# OSC_PLL_SARDC_OPTeFUSE.net
KiCad netlist of a schematic drawn in Altium Designer
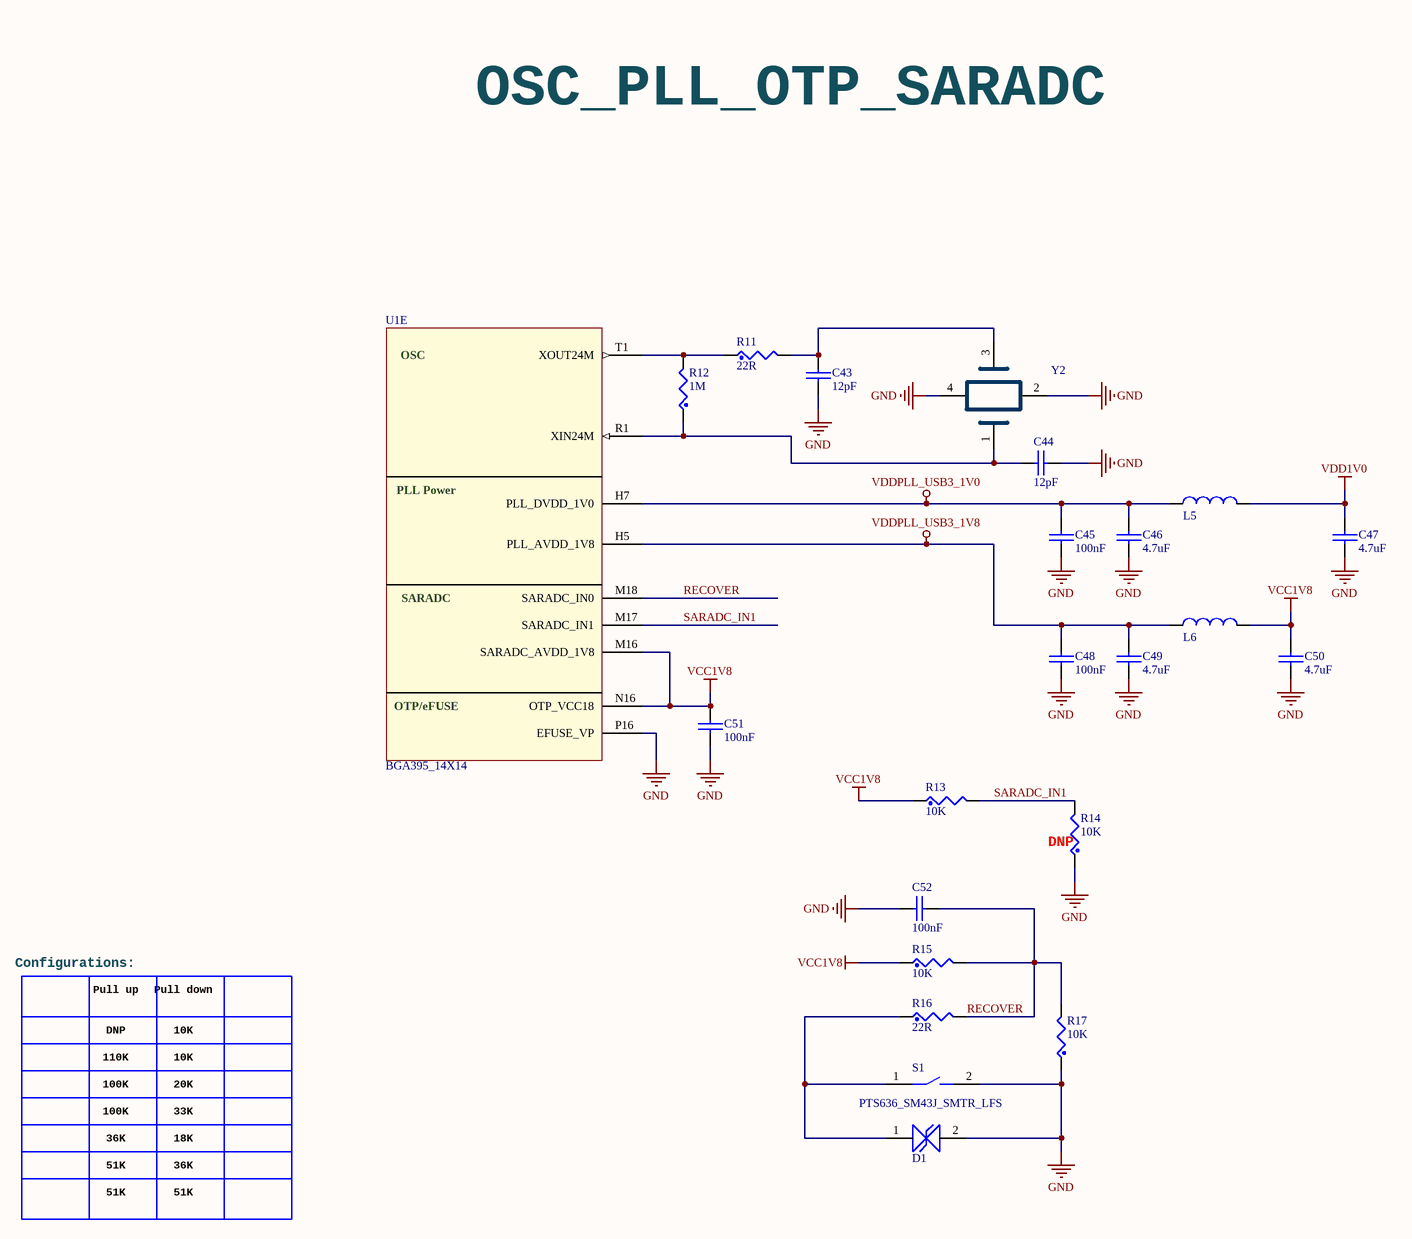
[diagram p0: OSC_PLL_SARDC_OPTeFUSE.SchDoc]

(export (version "E")
  (design (tool "Eeschema 10.0.6"))
  (components
    (comp (ref "C43")
      (value "12pF")
      (footprint "0402_CC - C")
      (libsource (lib "AAR_RockChip_RK3328") (part "CAP_NP"))
    )
    (comp (ref "C44")
      (value "12pF")
      (footprint "0402_CC - C")
      (libsource (lib "AAR_RockChip_RK3328") (part "CAP_NP"))
    )
    (comp (ref "C45")
      (value "100nF")
      (footprint "0402_CC - C")
      (libsource (lib "AAR_RockChip_RK3328") (part "CAP_NP"))
    )
    (comp (ref "C46")
      (value "4.7uF")
      (footprint "0402_CC - C")
      (libsource (lib "AAR_RockChip_RK3328") (part "CAP_NP"))
    )
    (comp (ref "C47")
      (value "4.7uF")
      (footprint "0402_CC - C")
      (libsource (lib "AAR_RockChip_RK3328") (part "CAP_NP"))
    )
    (comp (ref "C48")
      (value "100nF")
      (footprint "0402_CC - C")
      (libsource (lib "AAR_RockChip_RK3328") (part "CAP_NP"))
    )
    (comp (ref "C49")
      (value "4.7uF")
      (footprint "0402_CC - C")
      (libsource (lib "AAR_RockChip_RK3328") (part "CAP_NP"))
    )
    (comp (ref "C50")
      (value "4.7uF")
      (footprint "0402_CC - C")
      (libsource (lib "AAR_RockChip_RK3328") (part "CAP_NP"))
    )
    (comp (ref "C51")
      (value "100nF")
      (footprint "0402_CC - C")
      (libsource (lib "AAR_RockChip_RK3328") (part "CAP_NP"))
    )
    (comp (ref "C52")
      (value "100nF")
      (footprint "0402_CC - C")
      (libsource (lib "AAR_RockChip_RK3328") (part "CAP_NP"))
    )
    (comp (ref "D1")
      (value "TVS")
      (footprint "SODFL100X45-2N")
      (fields (field (name "MFR_PART_NO") "ESD5451N-2/TR") (field (name "LCSC PART #") "C239604"))
      (libsource (lib "AAR_RockChip_RK3328") (part "ESD5451N"))
    )
    (comp (ref "L5")
      (value "INDCHIP")
      (footprint "0603_C_Inductor")
      (description "Fixed Inductors  TDK, By AAR")
      (libsource (lib "AAR_RockChip_RK3328") (part "INDCHIP"))
    )
    (comp (ref "L6")
      (value "INDCHIP")
      (footprint "0603_C_Inductor")
      (description "Fixed Inductors  TDK, By AAR")
      (libsource (lib "AAR_RockChip_RK3328") (part "INDCHIP"))
    )
    (comp (ref "R11")
      (value "22R")
      (footprint "0402_CR")
      (libsource (lib "AAR_RockChip_RK3328") (part "RES"))
    )
    (comp (ref "R12") (value "1M") (footprint "0402_CR") (libsource (lib "AAR_RockChip_RK3328") (part "RES")))
    (comp (ref "R13")
      (value "10K")
      (footprint "0402_CR")
      (libsource (lib "AAR_RockChip_RK3328") (part "RES"))
    )
    (comp (ref "R14")
      (value "10K")
      (footprint "0402_CR")
      (libsource (lib "AAR_RockChip_RK3328") (part "RES"))
    )
    (comp (ref "R15")
      (value "10K")
      (footprint "0402_CR")
      (libsource (lib "AAR_RockChip_RK3328") (part "RES"))
    )
    (comp (ref "R16")
      (value "22R")
      (footprint "0402_CR")
      (libsource (lib "AAR_RockChip_RK3328") (part "RES"))
    )
    (comp (ref "R17")
      (value "10K")
      (footprint "0402_CR")
      (libsource (lib "AAR_RockChip_RK3328") (part "RES"))
    )
    (comp (ref "S1")
      (value "PTS636_SM43J_SMTR_LFS")
      (footprint "PTS636_3.5_6_4.3")
      (description "Tactile Switches Tact 50mA 12VDC, 6.0x3.5, 4.3mm H, 180gf, J leads, No ground pin, Black Actuator")
      (fields (field (name "MFR_PART_NO") "PTS636 SM43J SMTR LFS"))
      (libsource (lib "AAR_RockChip_RK3328") (part "PTS636"))
    )
    (comp (ref "U1")
      (value "BGA395_14X14")
      (footprint "BGA395C65P21X21_1750X1750X117")
      (description "By AAR")
      (libsource (lib "AAR_RockChip_RK3328") (part "RK3328"))
    )
    (comp (ref "Y2")
      (value "7R-24.000MEEC-T")
      (footprint "7R24000MEECT")
      (description "AAR, Crystal or Oscillator")
      (fields (field (name "MFR") "TXC"))
      (libsource (lib "AAR_RockChip_RK3328") (part "7R-24.000MEEC-T"))
    )
  )
  (nets
    (net (code "1") (name "/RECOVER") (class "Default")
      (node (ref "C52") (pin "2") (pinfunction "2_2") (pintype "passive"))
      (node (ref "R15") (pin "2") (pinfunction "2_2") (pintype "passive"))
      (node (ref "R16") (pin "2") (pinfunction "2_2") (pintype "passive"))
      (node (ref "R17") (pin "2") (pinfunction "2_2") (pintype "passive"))
      (node (ref "U1") (pin "M18") (pinfunction "SARADC_IN0_M18") (pintype "passive"))
    )
    (net (code "2") (name "/SARADC_IN1") (class "Default")
      (node (ref "R13") (pin "2") (pinfunction "2_2") (pintype "passive"))
      (node (ref "R14") (pin "2") (pinfunction "2_2") (pintype "passive"))
      (node (ref "U1") (pin "M17") (pinfunction "SARADC_IN1_M17") (pintype "passive"))
    )
    (net (code "3") (name "GND") (class "Default")
      (node (ref "C43") (pin "1") (pinfunction "1_1") (pintype "passive"))
      (node (ref "C44") (pin "1") (pinfunction "1_1") (pintype "passive"))
      (node (ref "C45") (pin "2") (pinfunction "2_2") (pintype "passive"))
      (node (ref "C46") (pin "2") (pinfunction "2_2") (pintype "passive"))
      (node (ref "C47") (pin "2") (pinfunction "2_2") (pintype "passive"))
      (node (ref "C48") (pin "2") (pinfunction "2_2") (pintype "passive"))
      (node (ref "C49") (pin "2") (pinfunction "2_2") (pintype "passive"))
      (node (ref "C50") (pin "2") (pinfunction "2_2") (pintype "passive"))
      (node (ref "C51") (pin "2") (pinfunction "2_2") (pintype "passive"))
      (node (ref "C52") (pin "1") (pinfunction "1_1") (pintype "passive"))
      (node (ref "D1") (pin "2") (pinfunction "2_2") (pintype "passive"))
      (node (ref "R14") (pin "1") (pinfunction "1_1") (pintype "passive"))
      (node (ref "R17") (pin "1") (pinfunction "1_1") (pintype "passive"))
      (node (ref "S1") (pin "2") (pinfunction "2_2") (pintype "passive"))
      (node (ref "U1") (pin "P16") (pinfunction "EFUSE_VP_P16") (pintype "open_collector"))
      (node (ref "Y2") (pin "2") (pinfunction "NC_1_2") (pintype "passive"))
      (node (ref "Y2") (pin "4") (pinfunction "NC_2_4") (pintype "passive"))
    )
    (net (code "4") (name "Net-(D1-Pad1)") (class "Default")
      (node (ref "D1") (pin "1") (pinfunction "1_1") (pintype "passive"))
      (node (ref "R16") (pin "1") (pinfunction "1_1") (pintype "passive"))
      (node (ref "S1") (pin "1") (pinfunction "1_1") (pintype "passive"))
    )
    (net (code "5") (name "Net-(U1E-XIN24M)") (class "Default")
      (node (ref "C44") (pin "2") (pinfunction "2_2") (pintype "passive"))
      (node (ref "R12") (pin "1") (pinfunction "1_1") (pintype "passive"))
      (node (ref "U1") (pin "R1") (pinfunction "XIN24M_R1") (pintype "input"))
      (node (ref "Y2") (pin "1") (pinfunction "X1_1_1") (pintype "passive"))
    )
    (net (code "6") (name "Net-(U1E-XOUT24M)") (class "Default")
      (node (ref "R11") (pin "1") (pinfunction "1_1") (pintype "passive"))
      (node (ref "R12") (pin "2") (pinfunction "2_2") (pintype "passive"))
      (node (ref "U1") (pin "T1") (pinfunction "XOUT24M_T1") (pintype "output"))
    )
    (net (code "7") (name "Net-(Y2-X1_2)") (class "Default")
      (node (ref "C43") (pin "2") (pinfunction "2_2") (pintype "passive"))
      (node (ref "R11") (pin "2") (pinfunction "2_2") (pintype "passive"))
      (node (ref "Y2") (pin "3") (pinfunction "X1_2_3") (pintype "passive"))
    )
    (net (code "8") (name "VCC1V8") (class "Default")
      (node (ref "C50") (pin "1") (pinfunction "1_1") (pintype "passive"))
      (node (ref "C51") (pin "1") (pinfunction "1_1") (pintype "passive"))
      (node (ref "L6") (pin "2") (pinfunction "2_2") (pintype "passive"))
      (node (ref "R13") (pin "1") (pinfunction "1_1") (pintype "passive"))
      (node (ref "R15") (pin "1") (pinfunction "1_1") (pintype "passive"))
      (node (ref "U1") (pin "M16") (pinfunction "SARADC_AVDD_1V8_M16") (pintype "power_in"))
      (node (ref "U1") (pin "N16") (pinfunction "OTP_VCC18_N16") (pintype "power_in"))
    )
    (net (code "9") (name "VDD1V0") (class "Default")
      (node (ref "C47") (pin "1") (pinfunction "1_1") (pintype "passive"))
      (node (ref "L5") (pin "2") (pinfunction "2_2") (pintype "passive"))
    )
    (net (code "10") (name "VDDPLL_USB3_1V0") (class "Default")
      (node (ref "C45") (pin "1") (pinfunction "1_1") (pintype "passive"))
      (node (ref "C46") (pin "1") (pinfunction "1_1") (pintype "passive"))
      (node (ref "L5") (pin "1") (pinfunction "1_1") (pintype "passive"))
      (node (ref "U1") (pin "H7") (pinfunction "PLL_DVDD_1V0_H7") (pintype "power_in"))
    )
    (net (code "11") (name "VDDPLL_USB3_1V8") (class "Default")
      (node (ref "C48") (pin "1") (pinfunction "1_1") (pintype "passive"))
      (node (ref "C49") (pin "1") (pinfunction "1_1") (pintype "passive"))
      (node (ref "L6") (pin "1") (pinfunction "1_1") (pintype "passive"))
      (node (ref "U1") (pin "H5") (pinfunction "PLL_AVDD_1V8_H5") (pintype "power_in"))
    )
  )
)
